# SensorNodeWithDisplay.net
KiCad netlist of a schematic drawn in EAGLE
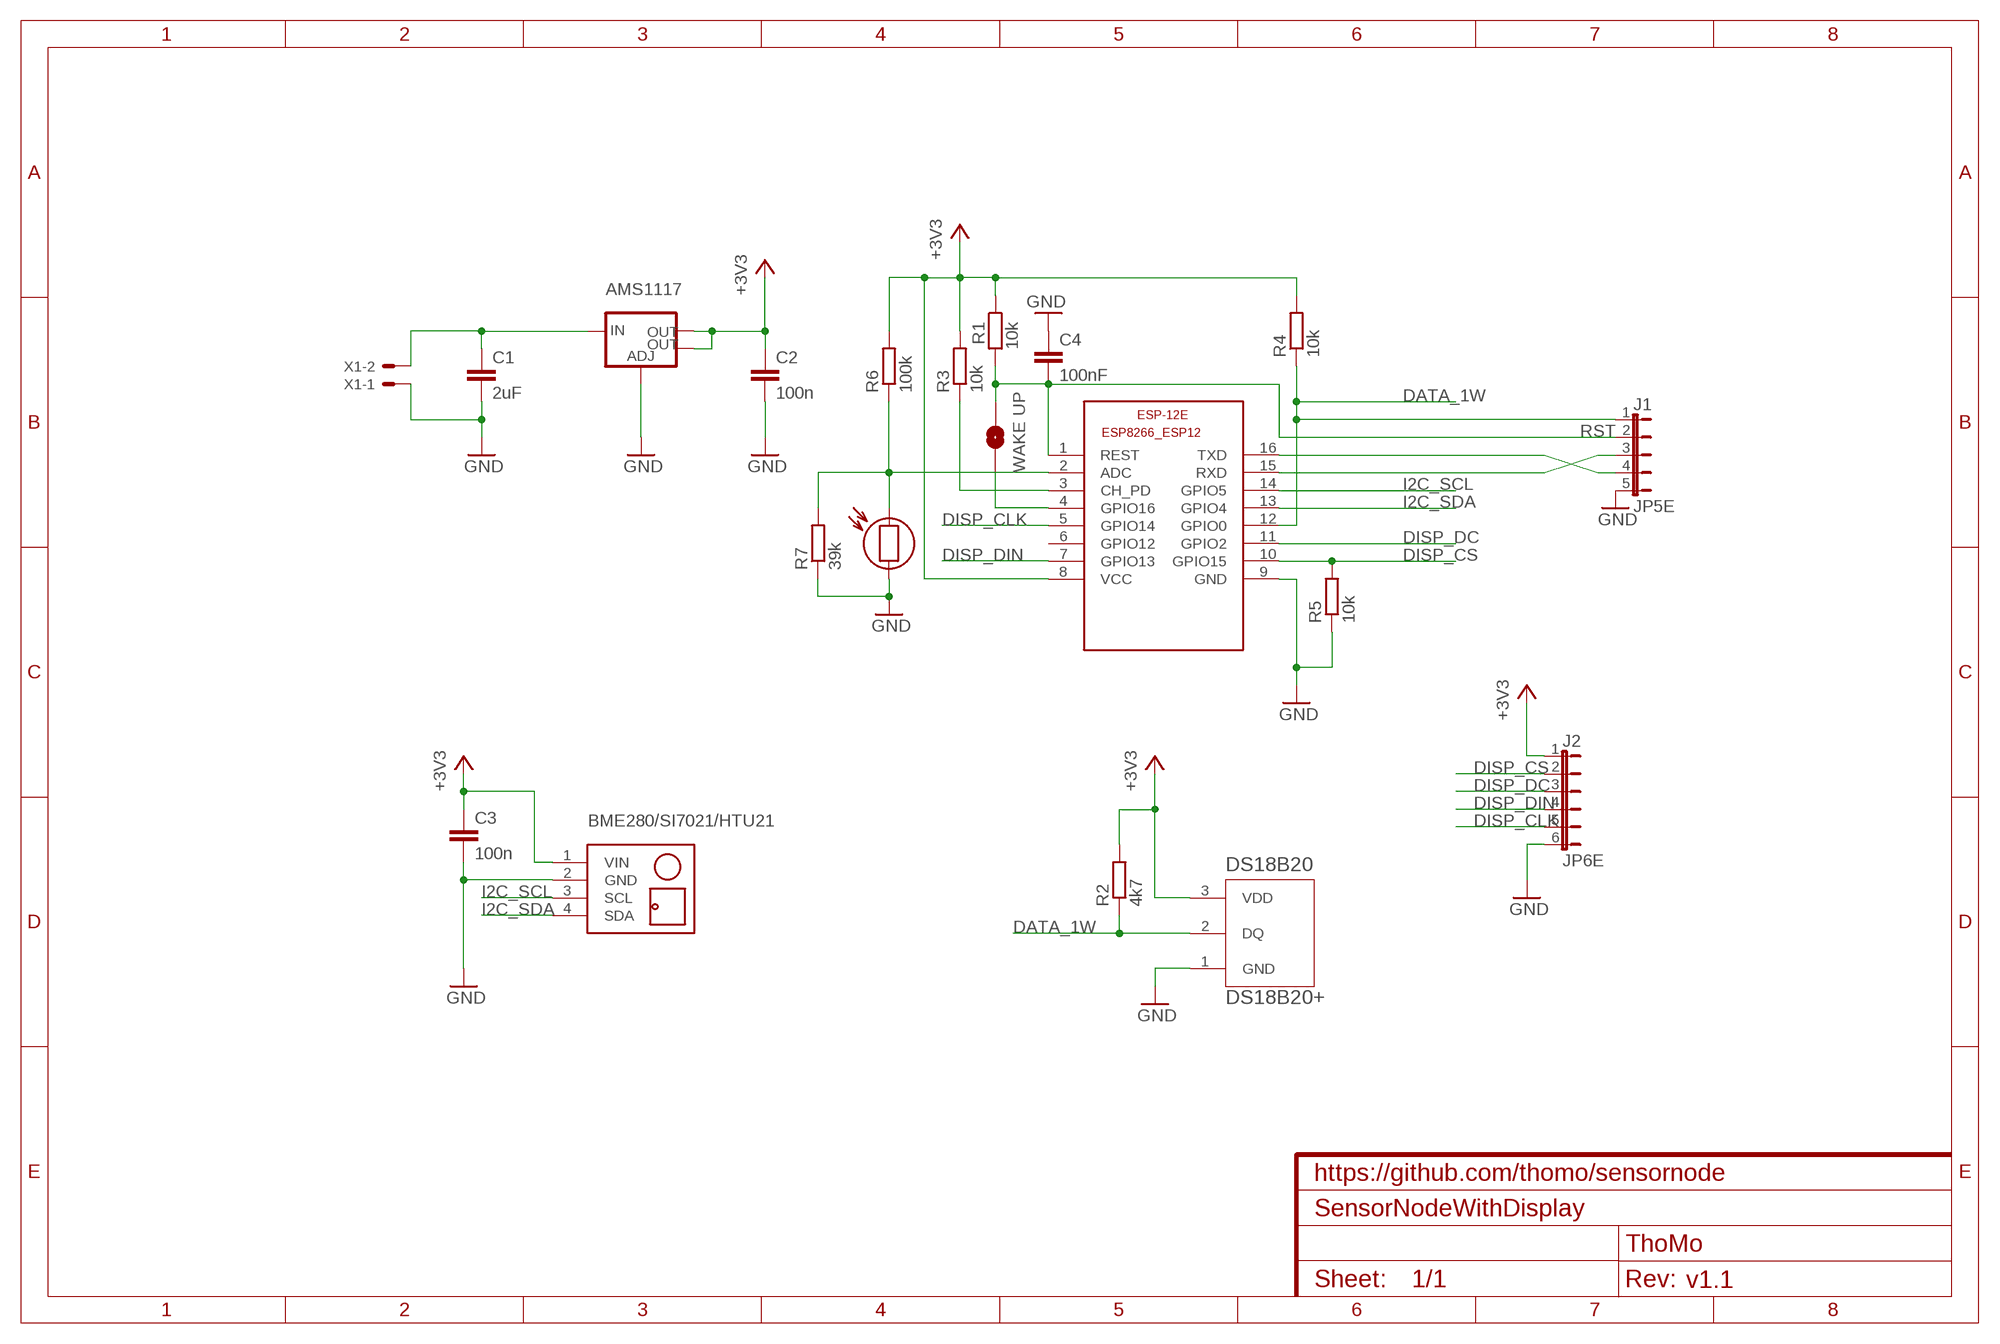
[diagram p0: schematic, sheet 1]

(export (version "E")
  (design (tool "Eeschema 10.0.6"))
  (components
    (comp (ref "AMS1117")
      (value "V_REG_LM1117SOT223")
      (footprint "eagle-import:SOT223")
      (libsource (lib "eagle-import") (part "V_REG_LM1117SOT223"))
    )
    (comp (ref "BME280/SI7021/HTU21")
      (value "BME280")
      (footprint "eagle-import:BME280")
      (libsource (lib "eagle-import") (part "BME280"))
    )
    (comp (ref "C1")
      (value "2uF")
      (footprint "eagle-import:C1206")
      (libsource (lib "eagle-import") (part "C-EUC1206"))
    )
    (comp (ref "C2")
      (value "100n")
      (footprint "eagle-import:C1206")
      (libsource (lib "eagle-import") (part "C-EUC1206"))
    )
    (comp (ref "C3")
      (value "100n")
      (footprint "eagle-import:C1206K")
      (libsource (lib "eagle-import") (part "C-EUC1206K"))
    )
    (comp (ref "C4")
      (value "100nF")
      (footprint "eagle-import:C1206")
      (libsource (lib "eagle-import") (part "C-EUC1206"))
    )
    (comp (ref "DS18B20")
      (value "DS18B20+")
      (footprint "eagle-import:TO-92")
      (libsource (lib "eagle-import") (part "DS18B20+"))
    )
    (comp (ref "ESP-12E")
      (value "ESP8266-12")
      (footprint "eagle-import:ESP8266-ESP12")
      (libsource (lib "eagle-import") (part "ESP8266-12"))
    )
    (comp (ref "J1")
      (value "JP5E")
      (footprint "eagle-import:JP5")
      (libsource (lib "eagle-import") (part "JP5E"))
    )
    (comp (ref "J2")
      (value "JP6E")
      (footprint "eagle-import:JP6")
      (libsource (lib "eagle-import") (part "JP6E"))
    )
    (comp (ref "LDR")
      (value "LDR-GL55XX")
      (footprint "eagle-import:GL55")
      (libsource (lib "eagle-import") (part "LDR-GL55XX"))
    )
    (comp (ref "R1")
      (value "10k")
      (footprint "eagle-import:M1206")
      (libsource (lib "eagle-import") (part "R-EU_M1206"))
    )
    (comp (ref "R2")
      (value "4k7")
      (footprint "eagle-import:M1206")
      (libsource (lib "eagle-import") (part "R-EU_M1206"))
    )
    (comp (ref "R3")
      (value "10k")
      (footprint "eagle-import:M1206")
      (libsource (lib "eagle-import") (part "R-EU_M1206"))
    )
    (comp (ref "R4")
      (value "10k")
      (footprint "eagle-import:M1206")
      (libsource (lib "eagle-import") (part "R-EU_M1206"))
    )
    (comp (ref "R5")
      (value "10k")
      (footprint "eagle-import:M1206")
      (libsource (lib "eagle-import") (part "R-EU_M1206"))
    )
    (comp (ref "R6")
      (value "100k")
      (footprint "eagle-import:M1206")
      (libsource (lib "eagle-import") (part "R-EU_M1206"))
    )
    (comp (ref "R7")
      (value "39k")
      (footprint "eagle-import:M1206")
      (libsource (lib "eagle-import") (part "R-EU_M1206"))
    )
    (comp (ref "WAKEUP")
      (value "WAKE UP")
      (footprint "eagle-import:SMT-JUMPER_2_NO_SILK")
      (libsource (lib "eagle-import") (part "JUMPER-SMT_2_NO_SILK"))
    )
    (comp (ref "X1")
      (value "JST-XH-02-PIN-LONG-PAD")
      (footprint "eagle-import:JST-XH-02-PACKAGE-LONG-PAD")
      (libsource (lib "eagle-import") (part "JST-XH-02-PIN-LONG-PAD"))
    )
  )
  (nets
    (net (code "1") (name "+3V3") (class "Default")
      (node (ref "AMS1117") (pin "2") (pinfunction "OUT_2") (pintype "output"))
      (node (ref "AMS1117") (pin "4") (pinfunction "OUT_4") (pintype "output"))
      (node (ref "BME280/SI7021/HTU21") (pin "1") (pinfunction "VIN_1") (pintype "power_in"))
      (node (ref "C2") (pin "1") (pinfunction "1_1") (pintype "passive"))
      (node (ref "C3") (pin "1") (pinfunction "1_1") (pintype "passive"))
      (node (ref "DS18B20") (pin "3") (pinfunction "VDD_3") (pintype "power_in"))
      (node (ref "ESP-12E") (pin "8") (pinfunction "VCC_8") (pintype "bidirectional"))
      (node (ref "J2") (pin "1") (pinfunction "1_1") (pintype "passive"))
      (node (ref "R1") (pin "1") (pinfunction "1_1") (pintype "passive"))
      (node (ref "R2") (pin "2") (pinfunction "2_2") (pintype "passive"))
      (node (ref "R3") (pin "2") (pinfunction "2_2") (pintype "passive"))
      (node (ref "R4") (pin "2") (pinfunction "2_2") (pintype "passive"))
      (node (ref "R6") (pin "2") (pinfunction "2_2") (pintype "passive"))
    )
    (net (code "2") (name "/DATA_1W") (class "Default")
      (node (ref "DS18B20") (pin "2") (pinfunction "DQ_2") (pintype "bidirectional"))
      (node (ref "ESP-12E") (pin "12") (pinfunction "GPIO0_12") (pintype "bidirectional"))
      (node (ref "J1") (pin "1") (pinfunction "1_1") (pintype "passive"))
      (node (ref "R2") (pin "1") (pinfunction "1_1") (pintype "passive"))
      (node (ref "R4") (pin "1") (pinfunction "1_1") (pintype "passive"))
    )
    (net (code "3") (name "/DISP_CLK") (class "Default")
      (node (ref "ESP-12E") (pin "5") (pinfunction "GPIO14_5") (pintype "bidirectional"))
      (node (ref "J2") (pin "5") (pinfunction "5_5") (pintype "passive"))
    )
    (net (code "4") (name "/DISP_CS") (class "Default")
      (node (ref "ESP-12E") (pin "10") (pinfunction "GPIO15_10") (pintype "bidirectional"))
      (node (ref "J2") (pin "2") (pinfunction "2_2") (pintype "passive"))
      (node (ref "R5") (pin "2") (pinfunction "2_2") (pintype "passive"))
    )
    (net (code "5") (name "/DISP_DC") (class "Default")
      (node (ref "ESP-12E") (pin "11") (pinfunction "GPIO2_11") (pintype "bidirectional"))
      (node (ref "J2") (pin "3") (pinfunction "3_3") (pintype "passive"))
    )
    (net (code "6") (name "/DISP_DIN") (class "Default")
      (node (ref "ESP-12E") (pin "7") (pinfunction "GPIO13_7") (pintype "bidirectional"))
      (node (ref "J2") (pin "4") (pinfunction "4_4") (pintype "passive"))
    )
    (net (code "7") (name "/I2C_SCL") (class "Default")
      (node (ref "BME280/SI7021/HTU21") (pin "3") (pinfunction "SCL_3") (pintype "bidirectional"))
      (node (ref "ESP-12E") (pin "14") (pinfunction "GPIO5_14") (pintype "bidirectional"))
    )
    (net (code "8") (name "/I2C_SDA") (class "Default")
      (node (ref "BME280/SI7021/HTU21") (pin "4") (pinfunction "SDA_4") (pintype "bidirectional"))
      (node (ref "ESP-12E") (pin "13") (pinfunction "GPIO4_13") (pintype "bidirectional"))
    )
    (net (code "9") (name "/RST") (class "Default")
      (node (ref "C4") (pin "2") (pinfunction "2_2") (pintype "passive"))
      (node (ref "ESP-12E") (pin "1") (pinfunction "REST_1") (pintype "bidirectional"))
      (node (ref "J1") (pin "2") (pinfunction "2_2") (pintype "passive"))
      (node (ref "R1") (pin "2") (pinfunction "2_2") (pintype "passive"))
      (node (ref "WAKEUP") (pin "2") (pinfunction "2_2") (pintype "passive"))
    )
    (net (code "10") (name "GND") (class "Default")
      (node (ref "AMS1117") (pin "1") (pinfunction "ADJ_1") (pintype "input"))
      (node (ref "BME280/SI7021/HTU21") (pin "2") (pinfunction "GND_2") (pintype "power_in"))
      (node (ref "C1") (pin "2") (pinfunction "2_2") (pintype "passive"))
      (node (ref "C2") (pin "2") (pinfunction "2_2") (pintype "passive"))
      (node (ref "C3") (pin "2") (pinfunction "2_2") (pintype "passive"))
      (node (ref "C4") (pin "1") (pinfunction "1_1") (pintype "passive"))
      (node (ref "DS18B20") (pin "1") (pinfunction "GND_1") (pintype "power_in"))
      (node (ref "ESP-12E") (pin "9") (pinfunction "GND_9") (pintype "bidirectional"))
      (node (ref "J1") (pin "5") (pinfunction "5_5") (pintype "passive"))
      (node (ref "J2") (pin "6") (pinfunction "6_6") (pintype "passive"))
      (node (ref "LDR") (pin "2") (pinfunction "2_2") (pintype "passive"))
      (node (ref "R5") (pin "1") (pinfunction "1_1") (pintype "passive"))
      (node (ref "R7") (pin "1") (pinfunction "1_1") (pintype "passive"))
      (node (ref "X1") (pin "1") (pinfunction "S_1") (pintype "passive"))
    )
    (net (code "11") (name "Net-(AMS1117-IN)") (class "Default")
      (node (ref "AMS1117") (pin "3") (pinfunction "IN_3") (pintype "input"))
      (node (ref "C1") (pin "1") (pinfunction "1_1") (pintype "passive"))
      (node (ref "X1") (pin "2") (pinfunction "S_2") (pintype "passive"))
    )
    (net (code "12") (name "Net-(ESP-12E-ADC)") (class "Default")
      (node (ref "ESP-12E") (pin "2") (pinfunction "ADC_2") (pintype "bidirectional"))
      (node (ref "LDR") (pin "1") (pinfunction "1_1") (pintype "passive"))
      (node (ref "R6") (pin "1") (pinfunction "1_1") (pintype "passive"))
      (node (ref "R7") (pin "2") (pinfunction "2_2") (pintype "passive"))
    )
    (net (code "13") (name "Net-(ESP-12E-CH_PD)") (class "Default")
      (node (ref "ESP-12E") (pin "3") (pinfunction "CH_PD_3") (pintype "bidirectional"))
      (node (ref "R3") (pin "1") (pinfunction "1_1") (pintype "passive"))
    )
    (net (code "14") (name "Net-(ESP-12E-GPIO16)") (class "Default")
      (node (ref "ESP-12E") (pin "4") (pinfunction "GPIO16_4") (pintype "bidirectional"))
      (node (ref "WAKEUP") (pin "1") (pinfunction "1_1") (pintype "passive"))
    )
    (net (code "15") (name "Net-(ESP-12E-RXD)") (class "Default")
      (node (ref "ESP-12E") (pin "15") (pinfunction "RXD_15") (pintype "bidirectional"))
      (node (ref "J1") (pin "3") (pinfunction "3_3") (pintype "passive"))
    )
    (net (code "16") (name "Net-(ESP-12E-TXD)") (class "Default")
      (node (ref "ESP-12E") (pin "16") (pinfunction "TXD_16") (pintype "bidirectional"))
      (node (ref "J1") (pin "4") (pinfunction "4_4") (pintype "passive"))
    )
    (net (code "17") (name "unconnected-(ESP-12E-GPIO12-Pad6)") (class "Default")
      (node (ref "ESP-12E") (pin "6") (pinfunction "GPIO12_6") (pintype "bidirectional"))
    )
  )
)
